# PX4IOARv1_2.net
KiCad netlist of a schematic drawn in EAGLE
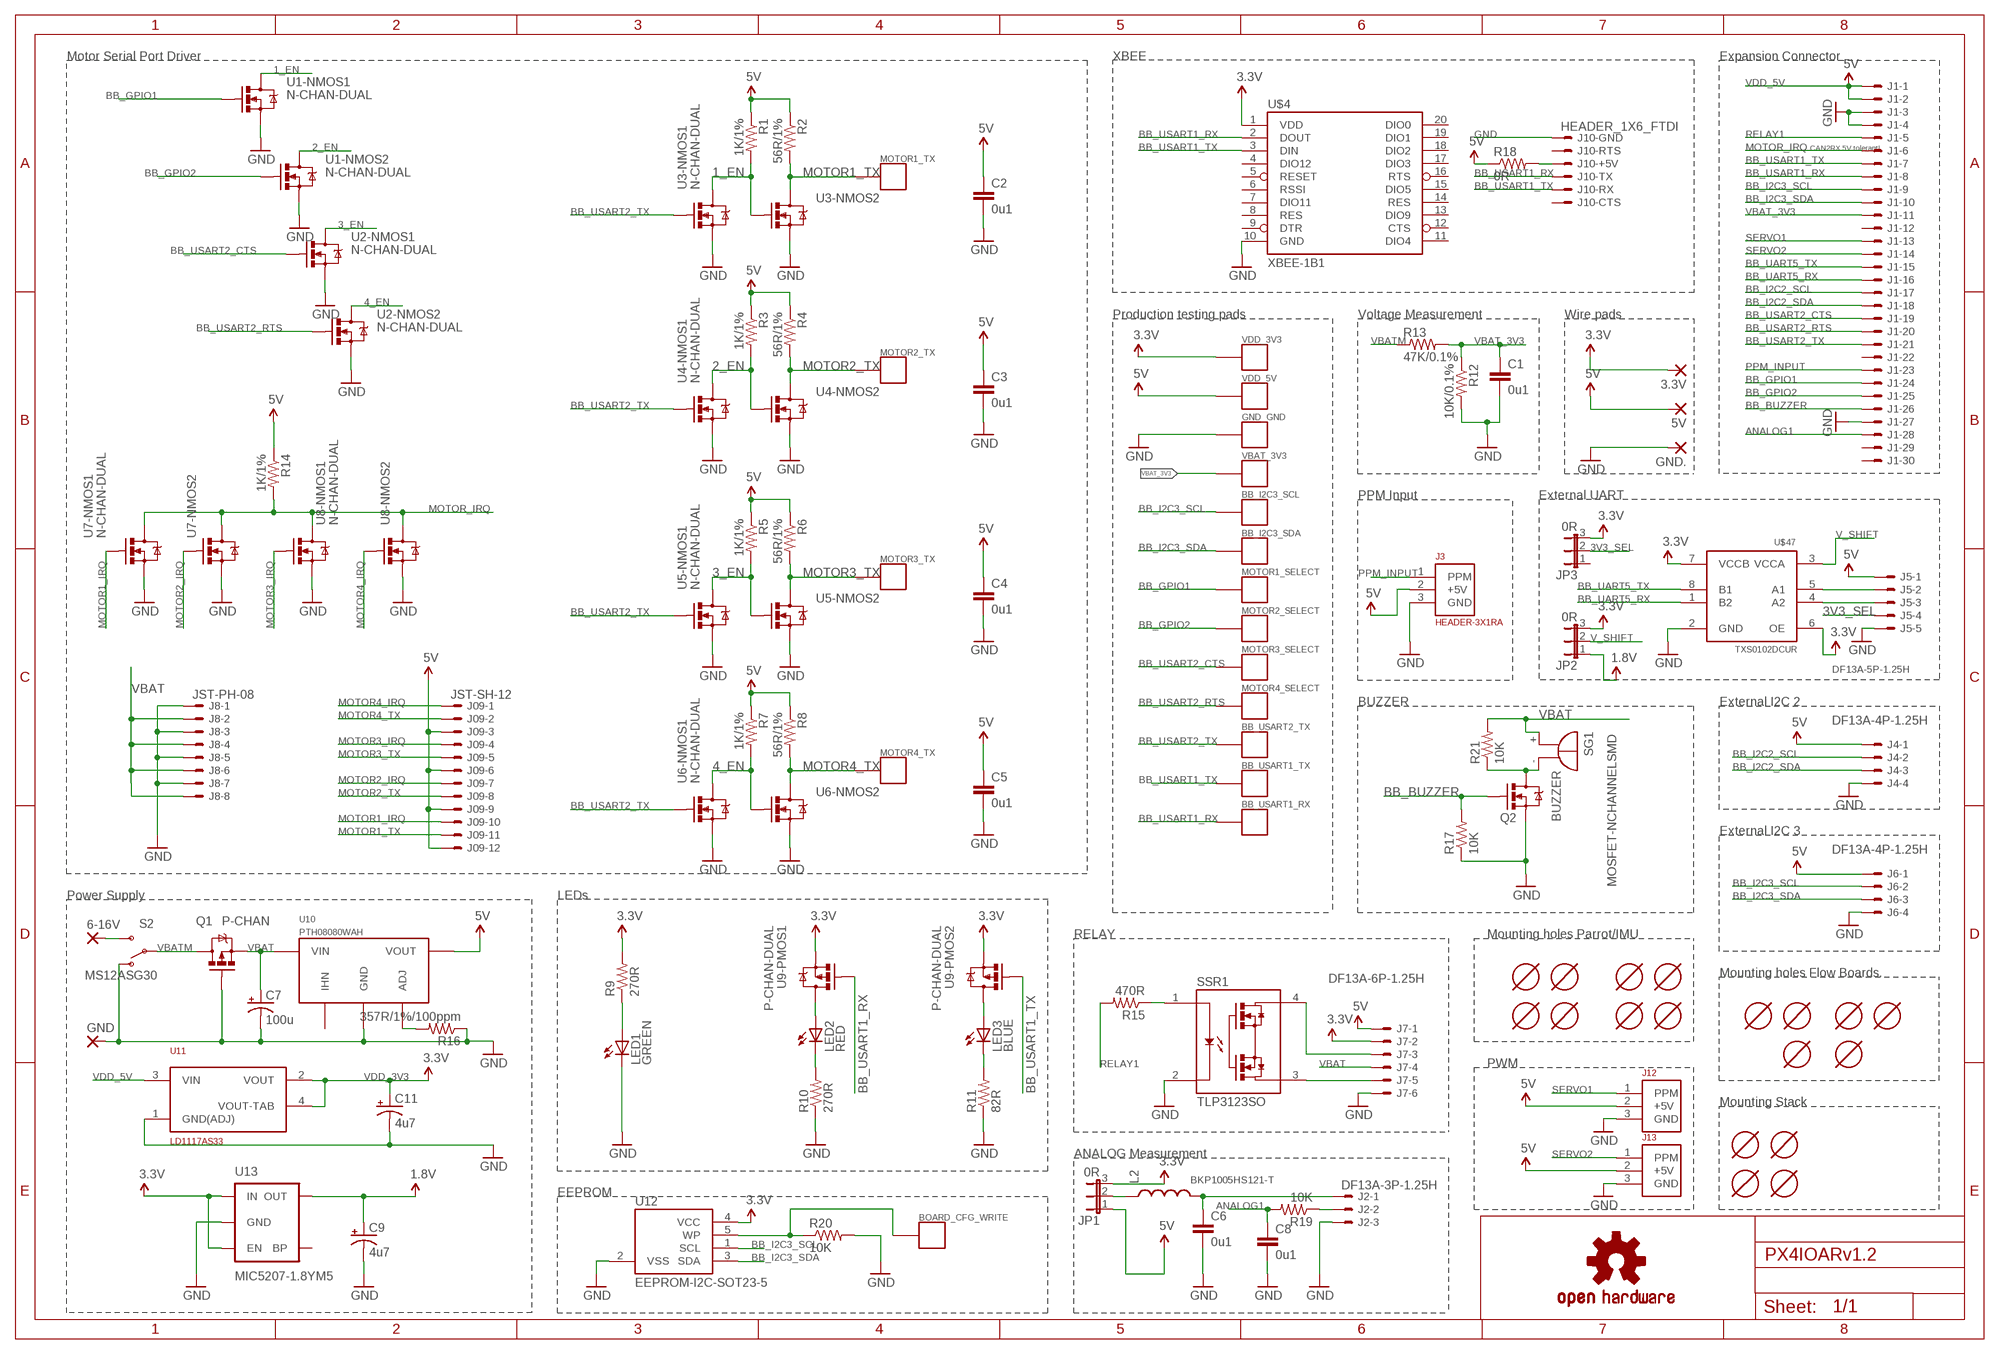
[diagram p0: schematic, sheet 1]

(export (version "E")
  (design (tool "Eeschema 10.0.6"))
  (components
    (comp (ref "3.3V")
      (value "WIREPADSMD3,5-2")
      (footprint "eagle-import:3,5-2")
      (libsource (lib "eagle-import") (part "WIREPADSMD3,5-2"))
    )
    (comp (ref "5V")
      (value "WIREPADSMD3,5-2")
      (footprint "eagle-import:3,5-2")
      (libsource (lib "eagle-import") (part "WIREPADSMD3,5-2"))
    )
    (comp (ref "6-16V")
      (value "WIREPADTH-2.0MM")
      (footprint "eagle-import:WIREPAD-TH-2.0MM")
      (libsource (lib "eagle-import") (part "WIREPADTH-2.0MM"))
    )
    (comp (ref "BB_I2C3_SCL")
      (value "PAD.05")
      (footprint "eagle-import:PAD.05X.05")
      (libsource (lib "eagle-import") (part "PAD.05"))
    )
    (comp (ref "BB_I2C3_SDA")
      (value "PAD.05")
      (footprint "eagle-import:PAD.05X.05")
      (libsource (lib "eagle-import") (part "PAD.05"))
    )
    (comp (ref "BB_USART1_RX")
      (value "PAD.05")
      (footprint "eagle-import:PAD.05X.05")
      (libsource (lib "eagle-import") (part "PAD.05"))
    )
    (comp (ref "BB_USART1_TX")
      (value "PAD.05")
      (footprint "eagle-import:PAD.05X.05")
      (libsource (lib "eagle-import") (part "PAD.05"))
    )
    (comp (ref "BB_USART2_TX")
      (value "PAD.05")
      (footprint "eagle-import:PAD.05X.05")
      (libsource (lib "eagle-import") (part "PAD.05"))
    )
    (comp (ref "BOARD_CFG_WRITE")
      (value "PAD.05")
      (footprint "eagle-import:PAD.05X.05")
      (libsource (lib "eagle-import") (part "PAD.05"))
    )
    (comp (ref "C1")
      (value "0u1")
      (footprint "eagle-import:0402-CAP")
      (fields (field (name "PARTNO") "CC0402ZRY5V7BB104"))
      (libsource (lib "eagle-import") (part "CAP0402-CAP"))
    )
    (comp (ref "C2")
      (value "0u1")
      (footprint "eagle-import:0402-CAP")
      (fields (field (name "PARTNO") "CC0402ZRY5V7BB104"))
      (libsource (lib "eagle-import") (part "CAP0402-CAP"))
    )
    (comp (ref "C3")
      (value "0u1")
      (footprint "eagle-import:0402-CAP")
      (fields (field (name "PARTNO") "CC0402ZRY5V7BB104"))
      (libsource (lib "eagle-import") (part "CAP0402-CAP"))
    )
    (comp (ref "C4")
      (value "0u1")
      (footprint "eagle-import:0402-CAP")
      (fields (field (name "PARTNO") "CC0402ZRY5V7BB104"))
      (libsource (lib "eagle-import") (part "CAP0402-CAP"))
    )
    (comp (ref "C5")
      (value "0u1")
      (footprint "eagle-import:0402-CAP")
      (fields (field (name "PARTNO") "CC0402ZRY5V7BB104"))
      (libsource (lib "eagle-import") (part "CAP0402-CAP"))
    )
    (comp (ref "C6")
      (value "0u1")
      (footprint "eagle-import:0402-CAP")
      (fields (field (name "PARTNO") "CC0402ZRY5V7BB104"))
      (libsource (lib "eagle-import") (part "CAP0402-CAP"))
    )
    (comp (ref "C7")
      (value "100u")
      (footprint "eagle-import:EIA7343")
      (fields (field (name "PARTNO") "T491X107K025ZT"))
      (libsource (lib "eagle-import") (part "CAP_POL7343"))
    )
    (comp (ref "C8")
      (value "0u1")
      (footprint "eagle-import:0402-CAP")
      (fields (field (name "PARTNO") "CC0402ZRY5V7BB104"))
      (libsource (lib "eagle-import") (part "CAP0402-CAP"))
    )
    (comp (ref "C9")
      (value "4u7")
      (footprint "eagle-import:EIA3216")
      (fields (field (name "PARTNO") "T491A475K010AT"))
      (libsource (lib "eagle-import") (part "CAP_POL1206"))
    )
    (comp (ref "C11")
      (value "4u7")
      (footprint "eagle-import:EIA3216")
      (fields (field (name "PARTNO") "T491A475K010AT"))
      (libsource (lib "eagle-import") (part "CAP_POL1206"))
    )
    (comp (ref "GND")
      (value "WIREPADTH-2.0MM")
      (footprint "eagle-import:WIREPAD-TH-2.0MM")
      (libsource (lib "eagle-import") (part "WIREPADTH-2.0MM"))
    )
    (comp (ref "GND.")
      (value "WIREPADSMD3,5-2")
      (footprint "eagle-import:3,5-2")
      (libsource (lib "eagle-import") (part "WIREPADSMD3,5-2"))
    )
    (comp (ref "GND_GND")
      (value "PAD.05")
      (footprint "eagle-import:PAD.05X.05")
      (libsource (lib "eagle-import") (part "PAD.05"))
    )
    (comp (ref "J1")
      (value "HEADER_2X15-REV")
      (footprint "eagle-import:HEADER_2MM_2X15_REVERSE")
      (fields (field (name "BOM") "INCLUDE") (field (name "PARTNO") "951230-2520-AR-PR"))
      (libsource (lib "eagle-import") (part "HEADER_2X15-REV"))
    )
    (comp (ref "J2")
      (value "DF13A-3P-1.25H")
      (footprint "eagle-import:DF13A-3P-1.25H")
      (fields (field (name "PARTNO") "DF13A-3P-1.25H(20)"))
      (libsource (lib "eagle-import") (part "DF13-3P-1.25?H"))
    )
    (comp (ref "J3")
      (value "HEADER-3X1RA")
      (footprint "eagle-import:3X1RA")
      (libsource (lib "eagle-import") (part "HEADER-3X1RA"))
    )
    (comp (ref "J4")
      (value "DF13A-4P-1.25H")
      (footprint "eagle-import:DF13A-4P-1.25H")
      (fields (field (name "PARTNO") "DF13A-4P-1.25H(20)"))
      (libsource (lib "eagle-import") (part "DF13-4P-1.25?H"))
    )
    (comp (ref "J5")
      (value "DF13A-5P-1.25H")
      (footprint "eagle-import:DF13A-5P-1.25H")
      (fields (field (name "PARTNO") "DF13A-5P-1.25H(20)"))
      (libsource (lib "eagle-import") (part "DF13-5P-1.25?H"))
    )
    (comp (ref "J6")
      (value "DF13A-4P-1.25H")
      (footprint "eagle-import:DF13A-4P-1.25H")
      (fields (field (name "PARTNO") "DF13A-4P-1.25H(20)"))
      (libsource (lib "eagle-import") (part "DF13-4P-1.25?H"))
    )
    (comp (ref "J7")
      (value "DF13A-6P-1.25H")
      (footprint "eagle-import:DF13A-6P-1.25H")
      (fields (field (name "PARTNO") "DF13A-6P-1.25H(20)"))
      (libsource (lib "eagle-import") (part "DF13-6P-1.25?H"))
    )
    (comp (ref "J8")
      (value "JST-PH-08")
      (footprint "eagle-import:B8B-PH-K-S")
      (fields (field (name "PARTNO") "B8B-PH-K-S(LF)(SN)"))
      (libsource (lib "eagle-import") (part "JST-PH-08"))
    )
    (comp (ref "J09")
      (value "JST-SH-12")
      (footprint "eagle-import:SM12B-SRSS-TB")
      (fields (field (name "PARTNO") "SM12B-SRSS-TB(LF)(SN)"))
      (libsource (lib "eagle-import") (part "JST-SH-12"))
    )
    (comp (ref "J10")
      (value "HEADER_1X6_FTDI")
      (footprint "eagle-import:HEADER_1X06-FTDI")
      (fields (field (name "BOM") "EXCLUDE"))
      (libsource (lib "eagle-import") (part "HEADER_1X6_FTDI"))
    )
    (comp (ref "J12")
      (value "HEADER-3X1SMD-BOARDEDGE")
      (footprint "eagle-import:HEADER_3X01_SMD_H_BOARD_EDGE")
      (libsource (lib "eagle-import") (part "HEADER-3X1SMD-BOARDEDGE"))
    )
    (comp (ref "J13")
      (value "HEADER-3X1SMD-BOARDEDGE")
      (footprint "eagle-import:HEADER_3X01_SMD_H_BOARD_EDGE")
      (libsource (lib "eagle-import") (part "HEADER-3X1SMD-BOARDEDGE"))
    )
    (comp (ref "JP1")
      (value "0R")
      (footprint "eagle-import:SJ_3_0603_PASTE1&2")
      (fields (field (name "PARTNO") "RMCF0402ZT0R00"))
      (libsource (lib "eagle-import") (part "JUMPER-30603"))
    )
    (comp (ref "JP2")
      (value "0R")
      (footprint "eagle-import:SJ_3_0603_PASTE1&2")
      (fields (field (name "PARTNO") "RMCF0402ZT0R00"))
      (libsource (lib "eagle-import") (part "JUMPER-30603"))
    )
    (comp (ref "JP3")
      (value "0R")
      (footprint "eagle-import:SJ_3_0603_PASTE1&2")
      (fields (field (name "PARTNO") "RMCF0402ZT0R00"))
      (libsource (lib "eagle-import") (part "JUMPER-30603"))
    )
    (comp (ref "L2")
      (value "BKP1005HS121-T")
      (footprint "eagle-import:0402-IND")
      (libsource (lib "eagle-import") (part "INDUCTOR0402"))
    )
    (comp (ref "LED1")
      (value "GREEN")
      (footprint "eagle-import:LED-0603")
      (fields (field (name "PARTNO") "LNJ337W83RA"))
      (libsource (lib "eagle-import") (part "LED0603"))
    )
    (comp (ref "LED2")
      (value "RED")
      (footprint "eagle-import:LED-0603")
      (fields (field (name "PARTNO") "LNJ237W82RA"))
      (libsource (lib "eagle-import") (part "LED0603"))
    )
    (comp (ref "LED3")
      (value "BLUE")
      (footprint "eagle-import:LED-0603")
      (fields (field (name "PARTNO") "LNJ937W8CRA"))
      (libsource (lib "eagle-import") (part "LED0603"))
    )
    (comp (ref "MOTOR1_SELECT")
      (value "PAD.05")
      (footprint "eagle-import:PAD.05X.05")
      (libsource (lib "eagle-import") (part "PAD.05"))
    )
    (comp (ref "MOTOR1_TX")
      (value "PAD.05")
      (footprint "eagle-import:PAD.05X.05")
      (libsource (lib "eagle-import") (part "PAD.05"))
    )
    (comp (ref "MOTOR2_SELECT")
      (value "PAD.05")
      (footprint "eagle-import:PAD.05X.05")
      (libsource (lib "eagle-import") (part "PAD.05"))
    )
    (comp (ref "MOTOR2_TX")
      (value "PAD.05")
      (footprint "eagle-import:PAD.05X.05")
      (libsource (lib "eagle-import") (part "PAD.05"))
    )
    (comp (ref "MOTOR3_SELECT")
      (value "PAD.05")
      (footprint "eagle-import:PAD.05X.05")
      (libsource (lib "eagle-import") (part "PAD.05"))
    )
    (comp (ref "MOTOR3_TX")
      (value "PAD.05")
      (footprint "eagle-import:PAD.05X.05")
      (libsource (lib "eagle-import") (part "PAD.05"))
    )
    (comp (ref "MOTOR4_SELECT")
      (value "PAD.05")
      (footprint "eagle-import:PAD.05X.05")
      (libsource (lib "eagle-import") (part "PAD.05"))
    )
    (comp (ref "MOTOR4_TX")
      (value "PAD.05")
      (footprint "eagle-import:PAD.05X.05")
      (libsource (lib "eagle-import") (part "PAD.05"))
    )
    (comp (ref "Q1")
      (value "P-CHAN")
      (footprint "eagle-import:DPAK")
      (fields (field (name "PARTNO") "IRFR5505TRPBF"))
      (libsource (lib "eagle-import") (part "MOSFET-PCHANNEL-DPAK"))
    )
    (comp (ref "Q2")
      (value "MOSFET-NCHANNELSMD")
      (footprint "eagle-import:SOT23-3")
      (fields (field (name "PARTNO") "ZXMS6004FFTA"))
      (libsource (lib "eagle-import") (part "MOSFET-NCHANNELSMD"))
    )
    (comp (ref "R1")
      (value "1K/1%")
      (footprint "eagle-import:0402-RES")
      (fields (field (name "PARTNO") "RMCF0402FT1K00"))
      (libsource (lib "eagle-import") (part "RESISTOR0402-RES"))
    )
    (comp (ref "R2")
      (value "56R/1%")
      (footprint "eagle-import:0402-RES")
      (fields (field (name "PARTNO") "ERJ-2RKF56R0X"))
      (libsource (lib "eagle-import") (part "RESISTOR0402-RES"))
    )
    (comp (ref "R3")
      (value "1K/1%")
      (footprint "eagle-import:0402-RES")
      (fields (field (name "PARTNO") "RMCF0402FT1K00"))
      (libsource (lib "eagle-import") (part "RESISTOR0402-RES"))
    )
    (comp (ref "R4")
      (value "56R/1%")
      (footprint "eagle-import:0402-RES")
      (fields (field (name "PARTNO") "ERJ-2RKF56R0X"))
      (libsource (lib "eagle-import") (part "RESISTOR0402-RES"))
    )
    (comp (ref "R5")
      (value "1K/1%")
      (footprint "eagle-import:0402-RES")
      (fields (field (name "PARTNO") "RMCF0402FT1K00"))
      (libsource (lib "eagle-import") (part "RESISTOR0402-RES"))
    )
    (comp (ref "R6")
      (value "56R/1%")
      (footprint "eagle-import:0402-RES")
      (fields (field (name "PARTNO") "ERJ-2RKF56R0X"))
      (libsource (lib "eagle-import") (part "RESISTOR0402-RES"))
    )
    (comp (ref "R7")
      (value "1K/1%")
      (footprint "eagle-import:0402-RES")
      (fields (field (name "PARTNO") "RMCF0402FT1K00"))
      (libsource (lib "eagle-import") (part "RESISTOR0402-RES"))
    )
    (comp (ref "R8")
      (value "56R/1%")
      (footprint "eagle-import:0402-RES")
      (fields (field (name "PARTNO") "ERJ-2RKF56R0X"))
      (libsource (lib "eagle-import") (part "RESISTOR0402-RES"))
    )
    (comp (ref "R9")
      (value "270R")
      (footprint "eagle-import:0402-RES")
      (fields (field (name "PARTNO") "RC0402JR-07270RL"))
      (libsource (lib "eagle-import") (part "RESISTOR0402-RES"))
    )
    (comp (ref "R10")
      (value "270R")
      (footprint "eagle-import:0402-RES")
      (fields (field (name "PARTNO") "RC0402JR-07270RL"))
      (libsource (lib "eagle-import") (part "RESISTOR0402-RES"))
    )
    (comp (ref "R11")
      (value "82R")
      (footprint "eagle-import:0402-RES")
      (fields (field (name "PARTNO") "RC0402JR-0782RL"))
      (libsource (lib "eagle-import") (part "RESISTOR0402-RES"))
    )
    (comp (ref "R12")
      (value "10K/0.1%")
      (footprint "eagle-import:0402-RES")
      (fields (field (name "PARTNO") "ERA-2AEB103X"))
      (libsource (lib "eagle-import") (part "RESISTOR0402-RES"))
    )
    (comp (ref "R13")
      (value "47K/0.1%")
      (footprint "eagle-import:0402-RES")
      (fields (field (name "PARTNO") "ERA-2AEB473X"))
      (libsource (lib "eagle-import") (part "RESISTOR0402-RES"))
    )
    (comp (ref "R14")
      (value "1K/1%")
      (footprint "eagle-import:0402-RES")
      (fields (field (name "PARTNO") "RMCF0402FT1K00"))
      (libsource (lib "eagle-import") (part "RESISTOR0402-RES"))
    )
    (comp (ref "R15")
      (value "470R")
      (footprint "eagle-import:0402-RES")
      (fields (field (name "PARTNO") "RC0402JR-07470RL"))
      (libsource (lib "eagle-import") (part "RESISTOR0402-RES"))
    )
    (comp (ref "R16")
      (value "357R/1%/100ppm")
      (footprint "eagle-import:0402-RES")
      (fields (field (name "PARTNO") "ERJ-2RKF3570X"))
      (libsource (lib "eagle-import") (part "RESISTOR0402-RES"))
    )
    (comp (ref "R17")
      (value "10K")
      (footprint "eagle-import:0402-RES")
      (fields (field (name "PARTNO") "RMCF0402FT10K0"))
      (libsource (lib "eagle-import") (part "RESISTOR0402-RES"))
    )
    (comp (ref "R18")
      (value "0R")
      (footprint "eagle-import:0402-RES")
      (fields (field (name "PARTNO") "RMCF0402ZT0R00"))
      (libsource (lib "eagle-import") (part "RESISTOR0402-RES"))
    )
    (comp (ref "R19")
      (value "10K")
      (footprint "eagle-import:0402-RES")
      (fields (field (name "PARTNO") "RMCF0402FT10K0"))
      (libsource (lib "eagle-import") (part "RESISTOR0402-RES"))
    )
    (comp (ref "R20")
      (value "10K")
      (footprint "eagle-import:0402-RES")
      (fields (field (name "PARTNO") "RMCF0402FT10K0"))
      (libsource (lib "eagle-import") (part "RESISTOR0402-RES"))
    )
    (comp (ref "R21")
      (value "10K")
      (footprint "eagle-import:0402-RES")
      (fields (field (name "PARTNO") "RMCF0402FT10K0"))
      (libsource (lib "eagle-import") (part "RESISTOR0402-RES"))
    )
    (comp (ref "S2")
      (value "MS12ASG30")
      (footprint "eagle-import:SWITCH-SPDT-TH-HORZ")
      (libsource (lib "eagle-import") (part "SWITCH-SPSTPTH-HORZ"))
    )
    (comp (ref "SG1")
      (value "BUZZER")
      (footprint "eagle-import:F_TMB")
      (fields (field (name "PARTNO") "PKM13EPYH4000-A0"))
      (libsource (lib "eagle-import") (part "BUZZER"))
    )
    (comp (ref "SSR1")
      (value "TLP3123SO")
      (footprint "eagle-import:SOP4-2.54")
      (fields (field (name "PARTNO") "TLP3123(F)"))
      (libsource (lib "eagle-import") (part "TLP3123SO"))
    )
    (comp (ref "U$1")
      (value "MOUNT-HOLE2.6MM")
      (footprint "eagle-import:MOUNT-HOLE2.6")
      (libsource (lib "eagle-import") (part "MOUNT-HOLE2.6MM"))
    )
    (comp (ref "U$4")
      (value "XBEE-1B1")
      (footprint "eagle-import:XBEE-1")
      (fields (field (name "PARTNO") "NPPN101BFCN-RC"))
      (libsource (lib "eagle-import") (part "XBEE-1B1"))
    )
    (comp (ref "U$6")
      (value "MOUNT-HOLE3.1MM")
      (footprint "eagle-import:MOUNT-HOLE3.1")
      (libsource (lib "eagle-import") (part "MOUNT-HOLE3.1MM"))
    )
    (comp (ref "U$7")
      (value "MOUNT-HOLE3.1MM")
      (footprint "eagle-import:MOUNT-HOLE3.1")
      (libsource (lib "eagle-import") (part "MOUNT-HOLE3.1MM"))
    )
    (comp (ref "U$8")
      (value "MOUNT-HOLE2.6MM")
      (footprint "eagle-import:MOUNT-HOLE2.6")
      (libsource (lib "eagle-import") (part "MOUNT-HOLE2.6MM"))
    )
    (comp (ref "U$9")
      (value "OSHW-LOGOM")
      (footprint "eagle-import:OSHW-LOGO-M")
      (libsource (lib "eagle-import") (part "OSHW-LOGOM"))
    )
    (comp (ref "U$17")
      (value "MOUNT-HOLE3.1MM")
      (footprint "eagle-import:MOUNT-HOLE3.1")
      (libsource (lib "eagle-import") (part "MOUNT-HOLE3.1MM"))
    )
    (comp (ref "U$19")
      (value "MOUNT-HOLE3.1MM")
      (footprint "eagle-import:MOUNT-HOLE3.1")
      (libsource (lib "eagle-import") (part "MOUNT-HOLE3.1MM"))
    )
    (comp (ref "U$21")
      (value "MOUNT-HOLE3.1MM")
      (footprint "eagle-import:MOUNT-HOLE3.1")
      (libsource (lib "eagle-import") (part "MOUNT-HOLE3.1MM"))
    )
    (comp (ref "U$29")
      (value "MOUNT-HOLE3.1MM")
      (footprint "eagle-import:MOUNT-HOLE3.1")
      (libsource (lib "eagle-import") (part "MOUNT-HOLE3.1MM"))
    )
    (comp (ref "U$30")
      (value "MOUNT-HOLE3.1MM")
      (footprint "eagle-import:MOUNT-HOLE3.1")
      (libsource (lib "eagle-import") (part "MOUNT-HOLE3.1MM"))
    )
    (comp (ref "U$31")
      (value "MOUNT-HOLE2.6MM")
      (footprint "eagle-import:MOUNT-HOLE2.6")
      (libsource (lib "eagle-import") (part "MOUNT-HOLE2.6MM"))
    )
    (comp (ref "U$32")
      (value "MOUNT-HOLE2.6MM")
      (footprint "eagle-import:MOUNT-HOLE2.6")
      (libsource (lib "eagle-import") (part "MOUNT-HOLE2.6MM"))
    )
    (comp (ref "U$33")
      (value "MOUNT-HOLE2.6MM")
      (footprint "eagle-import:MOUNT-HOLE2.6")
      (libsource (lib "eagle-import") (part "MOUNT-HOLE2.6MM"))
    )
    (comp (ref "U$34")
      (value "MOUNT-HOLE2.6MM")
      (footprint "eagle-import:MOUNT-HOLE2.6")
      (libsource (lib "eagle-import") (part "MOUNT-HOLE2.6MM"))
    )
    (comp (ref "U$40")
      (value "MOUNT-HOLE3.1MM")
      (footprint "eagle-import:MOUNT-HOLE3.1")
      (libsource (lib "eagle-import") (part "MOUNT-HOLE3.1MM"))
    )
    (comp (ref "U$43")
      (value "MOUNT-HOLE3.1MM")
      (footprint "eagle-import:MOUNT-HOLE3.1")
      (libsource (lib "eagle-import") (part "MOUNT-HOLE3.1MM"))
    )
    (comp (ref "U$44")
      (value "MOUNT-HOLE3.1MM")
      (footprint "eagle-import:MOUNT-HOLE3.1")
      (libsource (lib "eagle-import") (part "MOUNT-HOLE3.1MM"))
    )
    (comp (ref "U$45")
      (value "MOUNT-HOLE3.1MM")
      (footprint "eagle-import:MOUNT-HOLE3.1")
      (libsource (lib "eagle-import") (part "MOUNT-HOLE3.1MM"))
    )
    (comp (ref "U$46")
      (value "MOUNT-HOLE3.1MM")
      (footprint "eagle-import:MOUNT-HOLE3.1")
      (libsource (lib "eagle-import") (part "MOUNT-HOLE3.1MM"))
    )
    (comp (ref "U$47")
      (value "TXS0102DCUR")
      (footprint "eagle-import:TI-DCU")
      (libsource (lib "eagle-import") (part "TXS0102DCUR"))
    )
    (comp (ref "U1")
      (value "N-CHAN-DUAL")
      (footprint "eagle-import:SOT363_PHILIPS")
      (fields (field (name "PARTNO") "2N7002PS,115"))
      (libsource (lib "eagle-import") (part "MOSFET-DUAL-NCHANNEL-SOT363"))
    )
    (comp (ref "U2")
      (value "N-CHAN-DUAL")
      (footprint "eagle-import:SOT363_PHILIPS")
      (fields (field (name "PARTNO") "2N7002PS,115"))
      (libsource (lib "eagle-import") (part "MOSFET-DUAL-NCHANNEL-SOT363"))
    )
    (comp (ref "U3")
      (value "N-CHAN-DUAL")
      (footprint "eagle-import:SOT363_PHILIPS")
      (fields (field (name "PARTNO") "2N7002PS,115"))
      (libsource (lib "eagle-import") (part "MOSFET-DUAL-NCHANNEL-SOT363"))
    )
    (comp (ref "U4")
      (value "N-CHAN-DUAL")
      (footprint "eagle-import:SOT363_PHILIPS")
      (fields (field (name "PARTNO") "2N7002PS,115"))
      (libsource (lib "eagle-import") (part "MOSFET-DUAL-NCHANNEL-SOT363"))
    )
    (comp (ref "U5")
      (value "N-CHAN-DUAL")
      (footprint "eagle-import:SOT363_PHILIPS")
      (fields (field (name "PARTNO") "2N7002PS,115"))
      (libsource (lib "eagle-import") (part "MOSFET-DUAL-NCHANNEL-SOT363"))
    )
    (comp (ref "U6")
      (value "N-CHAN-DUAL")
      (footprint "eagle-import:SOT363_PHILIPS")
      (fields (field (name "PARTNO") "2N7002PS,115"))
      (libsource (lib "eagle-import") (part "MOSFET-DUAL-NCHANNEL-SOT363"))
    )
    (comp (ref "U7")
      (value "N-CHAN-DUAL")
      (footprint "eagle-import:SOT363_PHILIPS")
      (fields (field (name "PARTNO") "2N7002PS,115"))
      (libsource (lib "eagle-import") (part "MOSFET-DUAL-NCHANNEL-SOT363"))
    )
    (comp (ref "U8")
      (value "N-CHAN-DUAL")
      (footprint "eagle-import:SOT363_PHILIPS")
      (fields (field (name "PARTNO") "2N7002PS,115"))
      (libsource (lib "eagle-import") (part "MOSFET-DUAL-NCHANNEL-SOT363"))
    )
    (comp (ref "U9")
      (value "P-CHAN-DUAL")
      (footprint "eagle-import:SOT363_PHILIPS")
      (fields (field (name "PARTNO") "BSS84DW-7-F"))
      (libsource (lib "eagle-import") (part "MOSFET-DUAL-PCHANNEL-SOT363"))
    )
    (comp (ref "U10")
      (value "PTH08080WAH")
      (footprint "eagle-import:PTH08080W_TH")
      (libsource (lib "eagle-import") (part "PTH08080WAH"))
    )
    (comp (ref "U11")
      (value "LD1117AS33")
      (footprint "eagle-import:SOT-223")
      (libsource (lib "eagle-import") (part "LD1117AS33"))
    )
    (comp (ref "U12")
      (value "EEPROM-I2C-SOT23-5")
      (footprint "eagle-import:SOT23-5")
      (fields (field (name "PARTNO") "24LC01BT-I/OT"))
      (libsource (lib "eagle-import") (part "EEPROM-I2C-?SOT23-5"))
    )
    (comp (ref "U13")
      (value "MIC5207-1.8YM5")
      (footprint "eagle-import:SOT23-5")
      (libsource (lib "eagle-import") (part "V_REG_LDOSMD"))
    )
    (comp (ref "VBAT_3V3")
      (value "PAD.05")
      (footprint "eagle-import:PAD.05X.05")
      (libsource (lib "eagle-import") (part "PAD.05"))
    )
    (comp (ref "VDD_3V3")
      (value "PAD.05")
      (footprint "eagle-import:PAD.05X.05")
      (libsource (lib "eagle-import") (part "PAD.05"))
    )
    (comp (ref "VDD_5V")
      (value "PAD.05")
      (footprint "eagle-import:PAD.05X.05")
      (libsource (lib "eagle-import") (part "PAD.05"))
    )
  )
  (nets
    (net (code "1") (name "/1_EN") (class "Default")
      (node (ref "R1") (pin "2") (pinfunction "2_2") (pintype "passive"))
      (node (ref "U1") (pin "6") (pinfunction "D_6") (pintype "passive"))
      (node (ref "U3") (pin "5") (pinfunction "G_5") (pintype "passive"))
      (node (ref "U3") (pin "6") (pinfunction "D_6") (pintype "passive"))
    )
    (net (code "2") (name "/2_EN") (class "Default")
      (node (ref "R3") (pin "2") (pinfunction "2_2") (pintype "passive"))
      (node (ref "U1") (pin "3") (pinfunction "D_3") (pintype "passive"))
      (node (ref "U4") (pin "5") (pinfunction "G_5") (pintype "passive"))
      (node (ref "U4") (pin "6") (pinfunction "D_6") (pintype "passive"))
    )
    (net (code "3") (name "/3V3_SEL") (class "Default")
      (node (ref "J5") (pin "4") (pinfunction "S_4") (pintype "passive"))
      (node (ref "JP3") (pin "2") (pinfunction "2_2") (pintype "passive"))
    )
    (net (code "4") (name "/3_EN") (class "Default")
      (node (ref "R5") (pin "2") (pinfunction "2_2") (pintype "passive"))
      (node (ref "U2") (pin "6") (pinfunction "D_6") (pintype "passive"))
      (node (ref "U5") (pin "5") (pinfunction "G_5") (pintype "passive"))
      (node (ref "U5") (pin "6") (pinfunction "D_6") (pintype "passive"))
    )
    (net (code "5") (name "/4_EN") (class "Default")
      (node (ref "R7") (pin "2") (pinfunction "2_2") (pintype "passive"))
      (node (ref "U2") (pin "3") (pinfunction "D_3") (pintype "passive"))
      (node (ref "U6") (pin "5") (pinfunction "G_5") (pintype "passive"))
      (node (ref "U6") (pin "6") (pinfunction "D_6") (pintype "passive"))
    )
    (net (code "6") (name "/ANALOG1") (class "Default")
      (node (ref "C8") (pin "1") (pinfunction "1_1") (pintype "passive"))
      (node (ref "J1") (pin "28") (pinfunction "S_28") (pintype "passive"))
      (node (ref "R19") (pin "2") (pinfunction "2_2") (pintype "passive"))
    )
    (net (code "7") (name "/BB_BUZZER") (class "Default")
      (node (ref "J1") (pin "26") (pinfunction "S_26") (pintype "passive"))
      (node (ref "Q2") (pin "1") (pinfunction "G_1") (pintype "passive"))
      (node (ref "R17") (pin "2") (pinfunction "2_2") (pintype "passive"))
    )
    (net (code "8") (name "/BB_GPIO1") (class "Default")
      (node (ref "J1") (pin "24") (pinfunction "S_24") (pintype "passive"))
      (node (ref "MOTOR1_SELECT") (pin "P$1") (pinfunction "P$1_P$1") (pintype "passive"))
      (node (ref "U1") (pin "2") (pinfunction "G_2") (pintype "passive"))
    )
    (net (code "9") (name "/BB_GPIO2") (class "Default")
      (node (ref "J1") (pin "25") (pinfunction "S_25") (pintype "passive"))
      (node (ref "MOTOR2_SELECT") (pin "P$1") (pinfunction "P$1_P$1") (pintype "passive"))
      (node (ref "U1") (pin "5") (pinfunction "G_5") (pintype "passive"))
    )
    (net (code "10") (name "/BB_I2C2_SCL") (class "Default")
      (node (ref "J1") (pin "17") (pinfunction "S_17") (pintype "passive"))
      (node (ref "J4") (pin "2") (pinfunction "S_2") (pintype "passive"))
    )
    (net (code "11") (name "/BB_I2C2_SDA") (class "Default")
      (node (ref "J1") (pin "18") (pinfunction "S_18") (pintype "passive"))
      (node (ref "J4") (pin "3") (pinfunction "S_3") (pintype "passive"))
    )
    (net (code "12") (name "/BB_I2C3_SCL") (class "Default")
      (node (ref "BB_I2C3_SCL") (pin "P$1") (pinfunction "P$1_P$1") (pintype "passive"))
      (node (ref "J1") (pin "9") (pinfunction "S_9") (pintype "passive"))
      (node (ref "J6") (pin "2") (pinfunction "S_2") (pintype "passive"))
      (node (ref "U12") (pin "1") (pinfunction "SCL_1") (pintype "bidirectional"))
    )
    (net (code "13") (name "/BB_I2C3_SDA") (class "Default")
      (node (ref "BB_I2C3_SDA") (pin "P$1") (pinfunction "P$1_P$1") (pintype "passive"))
      (node (ref "J1") (pin "10") (pinfunction "S_10") (pintype "passive"))
      (node (ref "J6") (pin "3") (pinfunction "S_3") (pintype "passive"))
      (node (ref "U12") (pin "3") (pinfunction "SDA_3") (pintype "bidirectional"))
    )
    (net (code "14") (name "/BB_UART5_RX") (class "Default")
      (node (ref "J1") (pin "16") (pinfunction "S_16") (pintype "passive"))
      (node (ref "U$47") (pin "1") (pinfunction "B2_1") (pintype "bidirectional"))
    )
    (net (code "15") (name "/BB_UART5_TX") (class "Default")
      (node (ref "J1") (pin "15") (pinfunction "S_15") (pintype "passive"))
      (node (ref "U$47") (pin "8") (pinfunction "B1_8") (pintype "bidirectional"))
    )
    (net (code "16") (name "/BB_USART1_RX") (class "Default")
      (node (ref "BB_USART1_RX") (pin "P$1") (pinfunction "P$1_P$1") (pintype "passive"))
      (node (ref "J1") (pin "8") (pinfunction "S_8") (pintype "passive"))
      (node (ref "J10") (pin "RX") (pinfunction "S_RX") (pintype "passive"))
      (node (ref "U$4") (pin "2") (pinfunction "DOUT_2") (pintype "output"))
      (node (ref "U9") (pin "5") (pinfunction "G_5") (pintype "passive"))
    )
    (net (code "17") (name "/BB_USART1_TX") (class "Default")
      (node (ref "BB_USART1_TX") (pin "P$1") (pinfunction "P$1_P$1") (pintype "passive"))
      (node (ref "J1") (pin "7") (pinfunction "S_7") (pintype "passive"))
      (node (ref "J10") (pin "TX") (pinfunction "S_TX") (pintype "passive"))
      (node (ref "U$4") (pin "3") (pinfunction "DIN_3") (pintype "input"))
      (node (ref "U9") (pin "2") (pinfunction "G_2") (pintype "passive"))
    )
    (net (code "18") (name "/BB_USART2_CTS") (class "Default")
      (node (ref "J1") (pin "19") (pinfunction "S_19") (pintype "passive"))
      (node (ref "MOTOR3_SELECT") (pin "P$1") (pinfunction "P$1_P$1") (pintype "passive"))
      (node (ref "U2") (pin "2") (pinfunction "G_2") (pintype "passive"))
    )
    (net (code "19") (name "/BB_USART2_RTS") (class "Default")
      (node (ref "J1") (pin "20") (pinfunction "S_20") (pintype "passive"))
      (node (ref "MOTOR4_SELECT") (pin "P$1") (pinfunction "P$1_P$1") (pintype "passive"))
      (node (ref "U2") (pin "5") (pinfunction "G_5") (pintype "passive"))
    )
    (net (code "20") (name "/BB_USART2_TX") (class "Default")
      (node (ref "BB_USART2_TX") (pin "P$1") (pinfunction "P$1_P$1") (pintype "passive"))
      (node (ref "J1") (pin "21") (pinfunction "S_21") (pintype "passive"))
      (node (ref "U3") (pin "2") (pinfunction "G_2") (pintype "passive"))
      (node (ref "U4") (pin "2") (pinfunction "G_2") (pintype "passive"))
      (node (ref "U5") (pin "2") (pinfunction "G_2") (pintype "passive"))
      (node (ref "U6") (pin "2") (pinfunction "G_2") (pintype "passive"))
    )
    (net (code "21") (name "/MOTOR1_IRQ") (class "Default")
      (node (ref "J09") (pin "10") (pinfunction "S_10") (pintype "passive"))
      (node (ref "U7") (pin "2") (pinfunction "G_2") (pintype "passive"))
    )
    (net (code "22") (name "/MOTOR1_TX") (class "Default")
      (node (ref "J09") (pin "11") (pinfunction "S_11") (pintype "passive"))
      (node (ref "MOTOR1_TX") (pin "P$1") (pinfunction "P$1_P$1") (pintype "passive"))
      (node (ref "R2") (pin "2") (pinfunction "2_2") (pintype "passive"))
      (node (ref "U3") (pin "3") (pinfunction "D_3") (pintype "passive"))
    )
    (net (code "23") (name "/MOTOR2_IRQ") (class "Default")
      (node (ref "J09") (pin "7") (pinfunction "S_7") (pintype "passive"))
      (node (ref "U7") (pin "5") (pinfunction "G_5") (pintype "passive"))
    )
    (net (code "24") (name "/MOTOR2_TX") (class "Default")
      (node (ref "J09") (pin "8") (pinfunction "S_8") (pintype "passive"))
      (node (ref "MOTOR2_TX") (pin "P$1") (pinfunction "P$1_P$1") (pintype "passive"))
      (node (ref "R4") (pin "2") (pinfunction "2_2") (pintype "passive"))
      (node (ref "U4") (pin "3") (pinfunction "D_3") (pintype "passive"))
    )
    (net (code "25") (name "/MOTOR3_IRQ") (class "Default")
      (node (ref "J09") (pin "4") (pinfunction "S_4") (pintype "passive"))
      (node (ref "U8") (pin "2") (pinfunction "G_2") (pintype "passive"))
    )
    (net (code "26") (name "/MOTOR3_TX") (class "Default")
      (node (ref "J09") (pin "5") (pinfunction "S_5") (pintype "passive"))
      (node (ref "MOTOR3_TX") (pin "P$1") (pinfunction "P$1_P$1") (pintype "passive"))
      (node (ref "R6") (pin "2") (pinfunction "2_2") (pintype "passive"))
      (node (ref "U5") (pin "3") (pinfunction "D_3") (pintype "passive"))
    )
    (net (code "27") (name "/MOTOR4_IRQ") (class "Default")
      (node (ref "J09") (pin "1") (pinfunction "S_1") (pintype "passive"))
      (node (ref "U8") (pin "5") (pinfunction "G_5") (pintype "passive"))
    )
    (net (code "28") (name "/MOTOR4_TX") (class "Default")
      (node (ref "J09") (pin "2") (pinfunction "S_2") (pintype "passive"))
      (node (ref "MOTOR4_TX") (pin "P$1") (pinfunction "P$1_P$1") (pintype "passive"))
      (node (ref "R8") (pin "2") (pinfunction "2_2") (pintype "passive"))
      (node (ref "U6") (pin "3") (pinfunction "D_3") (pintype "passive"))
    )
    (net (code "29") (name "/MOTOR_IRQ") (class "Default")
      (node (ref "J1") (pin "6") (pinfunction "S_6") (pintype "passive"))
      (node (ref "R14") (pin "2") (pinfunction "2_2") (pintype "passive"))
      (node (ref "U7") (pin "3") (pinfunction "D_3") (pintype "passive"))
      (node (ref "U7") (pin "6") (pinfunction "D_6") (pintype "passive"))
      (node (ref "U8") (pin "3") (pinfunction "D_3") (pintype "passive"))
      (node (ref "U8") (pin "6") (pinfunction "D_6") (pintype "passive"))
    )
    (net (code "30") (name "/PPM_INPUT") (class "Default")
      (node (ref "J1") (pin "23") (pinfunction "S_23") (pintype "passive"))
      (node (ref "J3") (pin "1") (pinfunction "PPM_1") (pintype "bidirectional"))
    )
    (net (code "31") (name "/RELAY1") (class "Default")
      (node (ref "J1") (pin "5") (pinfunction "S_5") (pintype "passive"))
      (node (ref "R15") (pin "2") (pinfunction "2_2") (pintype "passive"))
    )
    (net (code "32") (name "/SERVO1") (class "Default")
      (node (ref "J1") (pin "13") (pinfunction "S_13") (pintype "passive"))
      (node (ref "J12") (pin "1") (pinfunction "PPM_1") (pintype "bidirectional"))
    )
    (net (code "33") (name "/SERVO2") (class "Default")
      (node (ref "J1") (pin "14") (pinfunction "S_14") (pintype "passive"))
      (node (ref "J13") (pin "1") (pinfunction "PPM_1") (pintype "bidirectional"))
    )
    (net (code "34") (name "/VBAT") (class "Default")
      (node (ref "C7") (pin "A") (pinfunction "+_A") (pintype "passive"))
      (node (ref "J7") (pin "4") (pinfunction "S_4") (pintype "passive"))
      (node (ref "J8") (pin "2") (pinfunction "S_2") (pintype "passive"))
      (node (ref "J8") (pin "4") (pinfunction "S_4") (pintype "passive"))
      (node (ref "J8") (pin "6") (pinfunction "S_6") (pintype "passive"))
      (node (ref "J8") (pin "8") (pinfunction "S_8") (pintype "passive"))
      (node (ref "Q1") (pin "3") (pinfunction "S_3") (pintype "passive"))
      (node (ref "R21") (pin "2") (pinfunction "2_2") (pintype "passive"))
      (node (ref "SG1") (pin "+") (pinfunction "+_+") (pintype "passive"))
      (node (ref "U10") (pin "1") (pinfunction "VIN_1") (pintype "power_in"))
    )
    (net (code "35") (name "/VBATM") (class "Default")
      (node (ref "Q1") (pin "4") (pinfunction "D_4") (pintype "passive"))
      (node (ref "R13") (pin "1") (pinfunction "1_1") (pintype "passive"))
      (node (ref "S2") (pin "2") (pinfunction "P_2") (pintype "passive"))
    )
    (net (code "36") (name "/V_SHIFT") (class "Default")
      (node (ref "JP2") (pin "2") (pinfunction "2_2") (pintype "passive"))
      (node (ref "U$47") (pin "3") (pinfunction "VCCA_3") (pintype "input"))
    )
    (net (code "37") (name "1.8V") (class "Default")
      (node (ref "C9") (pin "A") (pinfunction "+_A") (pintype "passive"))
      (node (ref "JP2") (pin "1") (pinfunction "1_1") (pintype "passive"))
      (node (ref "U13") (pin "5") (pinfunction "OUT_5") (pintype "passive"))
    )
    (net (code "38") (name "3.3V") (class "Default")
      (node (ref "3.3V") (pin "1") (pinfunction "P_1") (pintype "passive"))
      (node (ref "C11") (pin "A") (pinfunction "+_A") (pintype "passive"))
      (node (ref "J7") (pin "2") (pinfunction "S_2") (pintype "passive"))
      (node (ref "JP1") (pin "3") (pinfunction "3_3") (pintype "passive"))
      (node (ref "JP2") (pin "3") (pinfunction "3_3") (pintype "passive"))
      (node (ref "JP3") (pin "3") (pinfunction "3_3") (pintype "passive"))
      (node (ref "R9") (pin "2") (pinfunction "2_2") (pintype "passive"))
      (node (ref "U$4") (pin "1") (pinfunction "VDD_1") (pintype "power_in"))
      (node (ref "U$47") (pin "6") (pinfunction "OE_6") (pintype "input"))
      (node (ref "U$47") (pin "7") (pinfunction "VCCB_7") (pintype "input"))
      (node (ref "U11") (pin "2") (pinfunction "VOUT_2") (pintype "bidirectional"))
      (node (ref "U11") (pin "4") (pinfunction "VOUT-TAB_4") (pintype "bidirectional"))
      (node (ref "U12") (pin "4") (pinfunction "VCC_4") (pintype "power_in"))
      (node (ref "U13") (pin "1") (pinfunction "IN_1") (pintype "input"))
      (node (ref "U13") (pin "3") (pinfunction "EN_3") (pintype "input"))
      (node (ref "U9") (pin "1") (pinfunction "S_1") (pintype "passive"))
      (node (ref "U9") (pin "4") (pinfunction "S_4") (pintype "passive"))
      (node (ref "VDD_3V3") (pin "P$1") (pinfunction "P$1_P$1") (pintype "passive"))
    )
    (net (code "39") (name "5V") (class "Default")
      (node (ref "5V") (pin "1") (pinfunction "P_1") (pintype "passive"))
      (node (ref "C2") (pin "1") (pinfunction "1_1") (pintype "passive"))
      (node (ref "C3") (pin "1") (pinfunction "1_1") (pintype "passive"))
      (node (ref "C4") (pin "1") (pinfunction "1_1") (pintype "passive"))
      (node (ref "C5") (pin "1") (pinfunction "1_1") (pintype "passive"))
      (node (ref "J09") (pin "12") (pinfunction "S_12") (pintype "passive"))
      (node (ref "J09") (pin "3") (pinfunction "S_3") (pintype "passive"))
      (node (ref "J09") (pin "6") (pinfunction "S_6") (pintype "passive"))
      (node (ref "J09") (pin "9") (pinfunction "S_9") (pintype "passive"))
      (node (ref "J1") (pin "1") (pinfunction "S_1") (pintype "passive"))
      (node (ref "J1") (pin "2") (pinfunction "S_2") (pintype "passive"))
      (node (ref "J12") (pin "2") (pinfunction "+5V_2") (pintype "bidirectional"))
      (node (ref "J13") (pin "2") (pinfunction "+5V_2") (pintype "bidirectional"))
      (node (ref "J3") (pin "2") (pinfunction "+5V_2") (pintype "bidirectional"))
      (node (ref "J4") (pin "1") (pinfunction "S_1") (pintype "passive"))
      (node (ref "J5") (pin "1") (pinfunction "S_1") (pintype "passive"))
      (node (ref "J6") (pin "1") (pinfunction "S_1") (pintype "passive"))
      (node (ref "J7") (pin "1") (pinfunction "S_1") (pintype "passive"))
      (node (ref "JP1") (pin "1") (pinfunction "1_1") (pintype "passive"))
      (node (ref "R1") (pin "1") (pinfunction "1_1") (pintype "passive"))
      (node (ref "R14") (pin "1") (pinfunction "1_1") (pintype "passive"))
      (node (ref "R18") (pin "1") (pinfunction "1_1") (pintype "passive"))
      (node (ref "R2") (pin "1") (pinfunction "1_1") (pintype "passive"))
      (node (ref "R3") (pin "1") (pinfunction "1_1") (pintype "passive"))
      (node (ref "R4") (pin "1") (pinfunction "1_1") (pintype "passive"))
      (node (ref "R5") (pin "1") (pinfunction "1_1") (pintype "passive"))
      (node (ref "R6") (pin "1") (pinfunction "1_1") (pintype "passive"))
      (node (ref "R7") (pin "1") (pinfunction "1_1") (pintype "passive"))
      (node (ref "R8") (pin "1") (pinfunction "1_1") (pintype "passive"))
      (node (ref "U10") (pin "3") (pinfunction "VOUT_3") (pintype "power_in"))
      (node (ref "U11") (pin "3") (pinfunction "VIN_3") (pintype "bidirectional"))
      (node (ref "VDD_5V") (pin "P$1") (pinfunction "P$1_P$1") (pintype "passive"))
    )
    (net (code "40") (name "GND") (class "Default")
      (node (ref "C1") (pin "2") (pinfunction "2_2") (pintype "passive"))
      (node (ref "C11") (pin "C") (pinfunction "-_C") (pintype "passive"))
      (node (ref "C2") (pin "2") (pinfunction "2_2") (pintype "passive"))
      (node (ref "C3") (pin "2") (pinfunction "2_2") (pintype "passive"))
      (node (ref "C4") (pin "2") (pinfunction "2_2") (pintype "passive"))
      (node (ref "C5") (pin "2") (pinfunction "2_2") (pintype "passive"))
      (node (ref "C6") (pin "2") (pinfunction "2_2") (pintype "passive"))
      (node (ref "C7") (pin "C") (pinfunction "-_C") (pintype "passive"))
      (node (ref "C8") (pin "2") (pinfunction "2_2") (pintype "passive"))
      (node (ref "C9") (pin "C") (pinfunction "-_C") (pintype "passive"))
      (node (ref "GND") (pin "1") (pinfunction "P_1") (pintype "passive"))
      (node (ref "GND.") (pin "1") (pinfunction "P_1") (pintype "passive"))
      (node (ref "GND_GND") (pin "P$1") (pinfunction "P$1_P$1") (pintype "passive"))
      (node (ref "J1") (pin "27") (pinfunction "S_27") (pintype "passive"))
      (node (ref "J1") (pin "3") (pinfunction "S_3") (pintype "passive"))
      (node (ref "J1") (pin "4") (pinfunction "S_4") (pintype "passive"))
      (node (ref "J10") (pin "GND") (pinfunction "S_GND") (pintype "passive"))
      (node (ref "J12") (pin "3") (pinfunction "GND_3") (pintype "bidirectional"))
      (node (ref "J13") (pin "3") (pinfunction "GND_3") (pintype "bidirectional"))
      (node (ref "J2") (pin "3") (pinfunction "S_3") (pintype "passive"))
      (node (ref "J3") (pin "3") (pinfunction "GND_3") (pintype "bidirectional"))
      (node (ref "J4") (pin "4") (pinfunction "S_4") (pintype "passive"))
      (node (ref "J5") (pin "5") (pinfunction "S_5") (pintype "passive"))
      (node (ref "J6") (pin "4") (pinfunction "S_4") (pintype "passive"))
      (node (ref "J7") (pin "6") (pinfunction "S_6") (pintype "passive"))
      (node (ref "J8") (pin "1") (pinfunction "S_1") (pintype "passive"))
      (node (ref "J8") (pin "3") (pinfunction "S_3") (pintype "passive"))
      (node (ref "J8") (pin "5") (pinfunction "S_5") (pintype "passive"))
      (node (ref "J8") (pin "7") (pinfunction "S_7") (pintype "passive"))
      (node (ref "LED1") (pin "C") (pinfunction "C_C") (pintype "passive"))
      (node (ref "Q1") (pin "1") (pinfunction "G_1") (pintype "passive"))
      (node (ref "Q2") (pin "2") (pinfunction "S_2") (pintype "passive"))
      (node (ref "R10") (pin "1") (pinfunction "1_1") (pintype "passive"))
      (node (ref "R11") (pin "1") (pinfunction "1_1") (pintype "passive"))
      (node (ref "R12") (pin "2") (pinfunction "2_2") (pintype "passive"))
      (node (ref "R16") (pin "1") (pinfunction "1_1") (pintype "passive"))
      (node (ref "R17") (pin "1") (pinfunction "1_1") (pintype "passive"))
      (node (ref "R20") (pin "2") (pinfunction "2_2") (pintype "passive"))
      (node (ref "S2") (pin "1") (pinfunction "O_1") (pintype "passive"))
      (node (ref "SSR1") (pin "2") (pinfunction "2_2") (pintype "bidirectional"))
      (node (ref "U$4") (pin "10") (pinfunction "GND_10") (pintype "power_in"))
      (node (ref "U$47") (pin "2") (pinfunction "GND_2") (pintype "power_in"))
      (node (ref "U1") (pin "1") (pinfunction "S_1") (pintype "passive"))
      (node (ref "U1") (pin "4") (pinfunction "S_4") (pintype "passive"))
      (node (ref "U10") (pin "2") (pinfunction "GND_2") (pintype "power_in"))
      (node (ref "U11") (pin "1") (pinfunction "GND(ADJ)_1") (pintype "bidirectional"))
      (node (ref "U12") (pin "2") (pinfunction "VSS_2") (pintype "power_in"))
      (node (ref "U13") (pin "2") (pinfunction "GND_2") (pintype "input"))
      (node (ref "U2") (pin "1") (pinfunction "S_1") (pintype "passive"))
      (node (ref "U2") (pin "4") (pinfunction "S_4") (pintype "passive"))
      (node (ref "U3") (pin "1") (pinfunction "S_1") (pintype "passive"))
      (node (ref "U3") (pin "4") (pinfunction "S_4") (pintype "passive"))
      (node (ref "U4") (pin "1") (pinfunction "S_1") (pintype "passive"))
      (node (ref "U4") (pin "4") (pinfunction "S_4") (pintype "passive"))
      (node (ref "U5") (pin "1") (pinfunction "S_1") (pintype "passive"))
      (node (ref "U5") (pin "4") (pinfunction "S_4") (pintype "passive"))
      (node (ref "U6") (pin "1") (pinfunction "S_1") (pintype "passive"))
      (node (ref "U6") (pin "4") (pinfunction "S_4") (pintype "passive"))
      (node (ref "U7") (pin "1") (pinfunction "S_1") (pintype "passive"))
      (node (ref "U7") (pin "4") (pinfunction "S_4") (pintype "passive"))
      (node (ref "U8") (pin "1") (pinfunction "S_1") (pintype "passive"))
      (node (ref "U8") (pin "4") (pinfunction "S_4") (pintype "passive"))
    )
    (net (code "41") (name "Net-(6-16V-P)") (class "Default")
      (node (ref "6-16V") (pin "1") (pinfunction "P_1") (pintype "passive"))
      (node (ref "S2") (pin "3") (pinfunction "S_3") (pintype "passive"))
    )
    (net (code "42") (name "Net-(J2A-S)") (class "Default")
      (node (ref "C6") (pin "1") (pinfunction "1_1") (pintype "passive"))
      (node (ref "J2") (pin "1") (pinfunction "S_1") (pintype "passive"))
      (node (ref "L2") (pin "2") (pinfunction "2_2") (pintype "passive"))
    )
    (net (code "43") (name "Net-(J2B-S)") (class "Default")
      (node (ref "J2") (pin "2") (pinfunction "S_2") (pintype "passive"))
      (node (ref "R19") (pin "1") (pinfunction "1_1") (pintype "passive"))
    )
    (net (code "44") (name "Net-(J5B-S)") (class "Default")
      (node (ref "J5") (pin "2") (pinfunction "S_2") (pintype "passive"))
      (node (ref "U$47") (pin "5") (pinfunction "A1_5") (pintype "bidirectional"))
    )
    (net (code "45") (name "Net-(J5C-S)") (class "Default")
      (node (ref "J5") (pin "3") (pinfunction "S_3") (pintype "passive"))
      (node (ref "U$47") (pin "4") (pinfunction "A2_4") (pintype "bidirectional"))
    )
    (net (code "46") (name "Net-(J7C-S)") (class "Default")
      (node (ref "J7") (pin "3") (pinfunction "S_3") (pintype "passive"))
      (node (ref "SSR1") (pin "4") (pinfunction "4_4") (pintype "bidirectional"))
    )
    (net (code "47") (name "Net-(J7E-S)") (class "Default")
      (node (ref "J7") (pin "5") (pinfunction "S_5") (pintype "passive"))
      (node (ref "SSR1") (pin "3") (pinfunction "3_3") (pintype "bidirectional"))
    )
    (net (code "48") (name "Net-(J10A-S)") (class "Default")
      (node (ref "J10") (pin "+5V") (pinfunction "S_+5V") (pintype "passive"))
      (node (ref "R18") (pin "2") (pinfunction "2_2") (pintype "passive"))
    )
    (net (code "49") (name "Net-(JP1-Pad2)") (class "Default")
      (node (ref "JP1") (pin "2") (pinfunction "2_2") (pintype "passive"))
      (node (ref "L2") (pin "1") (pinfunction "1_1") (pintype "passive"))
    )
    (net (code "50") (name "Net-(LED1-PadA)") (class "Default")
      (node (ref "LED1") (pin "A") (pinfunction "A_A") (pintype "passive"))
      (node (ref "R9") (pin "1") (pinfunction "1_1") (pintype "passive"))
    )
    (net (code "51") (name "Net-(LED2-PadC)") (class "Default")
      (node (ref "LED2") (pin "C") (pinfunction "C_C") (pintype "passive"))
      (node (ref "R10") (pin "2") (pinfunction "2_2") (pintype "passive"))
    )
    (net (code "52") (name "Net-(LED3-PadC)") (class "Default")
      (node (ref "LED3") (pin "C") (pinfunction "C_C") (pintype "passive"))
      (node (ref "R11") (pin "2") (pinfunction "2_2") (pintype "passive"))
    )
    (net (code "53") (name "Net-(Q2-D)") (class "Default")
      (node (ref "Q2") (pin "3") (pinfunction "D_3") (pintype "passive"))
      (node (ref "R21") (pin "1") (pinfunction "1_1") (pintype "passive"))
      (node (ref "SG1") (pin "-") (pinfunction "-_-") (pintype "passive"))
    )
    (net (code "54") (name "Net-(R15-Pad1)") (class "Default")
      (node (ref "R15") (pin "1") (pinfunction "1_1") (pintype "passive"))
      (node (ref "SSR1") (pin "1") (pinfunction "1_1") (pintype "bidirectional"))
    )
    (net (code "55") (name "Net-(U9A-D)") (class "Default")
      (node (ref "LED2") (pin "A") (pinfunction "A_A") (pintype "passive"))
      (node (ref "U9") (pin "3") (pinfunction "D_3") (pintype "passive"))
    )
    (net (code "56") (name "Net-(U9B-D)") (class "Default")
      (node (ref "LED3") (pin "A") (pinfunction "A_A") (pintype "passive"))
      (node (ref "U9") (pin "6") (pinfunction "D_6") (pintype "passive"))
    )
    (net (code "57") (name "Net-(U10-ADJ)") (class "Default")
      (node (ref "R16") (pin "2") (pinfunction "2_2") (pintype "passive"))
      (node (ref "U10") (pin "4") (pinfunction "ADJ_4") (pintype "bidirectional"))
    )
    (net (code "58") (name "Net-(U12-WP)") (class "Default")
      (node (ref "BOARD_CFG_WRITE") (pin "P$1") (pinfunction "P$1_P$1") (pintype "passive"))
      (node (ref "R20") (pin "1") (pinfunction "1_1") (pintype "passive"))
      (node (ref "U12") (pin "5") (pinfunction "WP_5") (pintype "bidirectional"))
    )
    (net (code "59") (name "VBAT_3V3") (class "Default")
      (node (ref "C1") (pin "1") (pinfunction "1_1") (pintype "passive"))
      (node (ref "J1") (pin "11") (pinfunction "S_11") (pintype "passive"))
      (node (ref "R12") (pin "1") (pinfunction "1_1") (pintype "passive"))
      (node (ref "R13") (pin "2") (pinfunction "2_2") (pintype "passive"))
      (node (ref "VBAT_3V3") (pin "P$1") (pinfunction "P$1_P$1") (pintype "passive"))
    )
    (net (code "60") (name "unconnected-(J1D-S-Pad12)") (class "Default")
      (node (ref "J1") (pin "12") (pinfunction "S_12") (pintype "passive"))
    )
    (net (code "61") (name "unconnected-(J1O-S-Pad22)") (class "Default")
      (node (ref "J1") (pin "22") (pinfunction "S_22") (pintype "passive"))
    )
    (net (code "62") (name "unconnected-(J1V-S-Pad29)") (class "Default")
      (node (ref "J1") (pin "29") (pinfunction "S_29") (pintype "passive"))
    )
    (net (code "63") (name "unconnected-(J1X-S-Pad30)") (class "Default")
      (node (ref "J1") (pin "30") (pinfunction "S_30") (pintype "passive"))
    )
    (net (code "64") (name "unconnected-(J10B-S-PadCTS)") (class "Default")
      (node (ref "J10") (pin "CTS") (pinfunction "S_CTS") (pintype "passive"))
    )
    (net (code "65") (name "unconnected-(J10D-S-PadRTS)") (class "Default")
      (node (ref "J10") (pin "RTS") (pinfunction "S_RTS") (pintype "passive"))
    )
    (net (code "66") (name "unconnected-(JP3-Pad1)") (class "Default")
      (node (ref "JP3") (pin "1") (pinfunction "1_1") (pintype "passive"))
    )
    (net (code "67") (name "unconnected-(U$4-CTS-Pad12)") (class "Default")
      (node (ref "U$4") (pin "12") (pinfunction "CTS_12") (pintype "output"))
    )
    (net (code "68") (name "unconnected-(U$4-DIO0-Pad20)") (class "Default")
      (node (ref "U$4") (pin "20") (pinfunction "DIO0_20") (pintype "bidirectional"))
    )
    (net (code "69") (name "unconnected-(U$4-DIO1-Pad19)") (class "Default")
      (node (ref "U$4") (pin "19") (pinfunction "DIO1_19") (pintype "bidirectional"))
    )
    (net (code "70") (name "unconnected-(U$4-DIO2-Pad18)") (class "Default")
      (node (ref "U$4") (pin "18") (pinfunction "DIO2_18") (pintype "bidirectional"))
    )
    (net (code "71") (name "unconnected-(U$4-DIO3-Pad17)") (class "Default")
      (node (ref "U$4") (pin "17") (pinfunction "DIO3_17") (pintype "bidirectional"))
    )
    (net (code "72") (name "unconnected-(U$4-DIO4-Pad11)") (class "Default")
      (node (ref "U$4") (pin "11") (pinfunction "DIO4_11") (pintype "bidirectional"))
    )
    (net (code "73") (name "unconnected-(U$4-DIO5-Pad15)") (class "Default")
      (node (ref "U$4") (pin "15") (pinfunction "DIO5_15") (pintype "bidirectional"))
    )
    (net (code "74") (name "unconnected-(U$4-DIO9-Pad13)") (class "Default")
      (node (ref "U$4") (pin "13") (pinfunction "DIO9_13") (pintype "bidirectional"))
    )
    (net (code "75") (name "unconnected-(U$4-DIO11-Pad7)") (class "Default")
      (node (ref "U$4") (pin "7") (pinfunction "DIO11_7") (pintype "bidirectional"))
    )
    (net (code "76") (name "unconnected-(U$4-DIO12-Pad4)") (class "Default")
      (node (ref "U$4") (pin "4") (pinfunction "DIO12_4") (pintype "bidirectional"))
    )
    (net (code "77") (name "unconnected-(U$4-DTR-Pad9)") (class "Default")
      (node (ref "U$4") (pin "9") (pinfunction "DTR_9") (pintype "bidirectional"))
    )
    (net (code "78") (name "unconnected-(U$4-RES-Pad8)") (class "Default")
      (node (ref "U$4") (pin "8") (pinfunction "RES_8") (pintype "bidirectional"))
    )
    (net (code "79") (name "unconnected-(U$4-RES-Pad14)") (class "Default")
      (node (ref "U$4") (pin "14") (pinfunction "RES_14") (pintype "bidirectional"))
    )
    (net (code "80") (name "unconnected-(U$4-RESET-Pad5)") (class "Default")
      (node (ref "U$4") (pin "5") (pinfunction "RESET_5") (pintype "input"))
    )
    (net (code "81") (name "unconnected-(U$4-RSSI-Pad6)") (class "Default")
      (node (ref "U$4") (pin "6") (pinfunction "RSSI_6") (pintype "bidirectional"))
    )
    (net (code "82") (name "unconnected-(U$4-RTS-Pad16)") (class "Default")
      (node (ref "U$4") (pin "16") (pinfunction "RTS_16") (pintype "input"))
    )
    (net (code "83") (name "unconnected-(U10-IHN-Pad5)") (class "Default")
      (node (ref "U10") (pin "5") (pinfunction "IHN_5") (pintype "bidirectional"))
    )
    (net (code "84") (name "unconnected-(U13-BP-Pad4)") (class "Default")
      (node (ref "U13") (pin "4") (pinfunction "BP_4") (pintype "input"))
    )
  )
)
